# C3_0-_-3_0-led_-24_10_17.net
KiCad netlist of a schematic drawn in Altium Designer
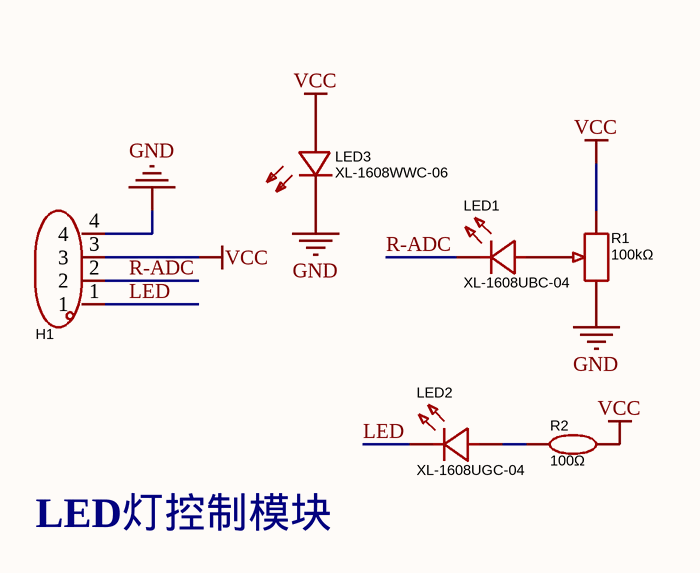
[diagram p0: C3.0-控制传感-3.0-led灯控制模块-24.10.17.SchDoc]

(export (version "E")
  (design (tool "Eeschema 10.0.6"))
  (components
    (comp (ref "H1")
      (value "PZ254V-11-04P")
      (footprint "HDR-TH_4P-P2.54-V-M")
      (fields (field (name "MANUFACTURER") "XFCN(兴飞)"))
      (libsource (lib "连接器") (part "PZ254V-11-04P"))
    )
    (comp (ref "LED1")
      (value "XL-1608UBC-04")
      (footprint "LED0603-RD_BLUE")
      (fields (field (name "MANUFACTURER") "XINGLIGHT(成兴光)"))
      (libsource (lib "外设") (part "XL-1608UBC-04"))
    )
    (comp (ref "LED2")
      (value "XL-1608UGC-04")
      (footprint "LED0603-RD_GREEN")
      (fields (field (name "MANUFACTURER") "XINGLIGHT(成兴光)"))
      (libsource (lib "外设") (part "XL-1608UGC-04"))
    )
    (comp (ref "LED3")
      (value "XL-1608WWC-06")
      (footprint "LED0603-RD_WHITE")
      (fields (field (name "MANUFACTURER") "XINGLIGHT(成兴光)"))
      (libsource (lib "外设") (part "XL-1608WWC-06"))
    )
    (comp (ref "R1")
      (value "100kΩ")
      (footprint "RES-ADJ-TH_3P-L9.5-W4.9-P2.50-L_3296W")
      (fields
        (field (name "MANUFACTURER") "BOCHEN(博晨)")
        (field (name "MANUFACTURER PART") "3296W-1-104")
        (field (name "TOLERANCE") "±10%")
      )
      (libsource (lib "电阻") (part "3296W-1-104"))
    )
    (comp (ref "R2")
      (value "100Ω")
      (footprint "R0805")
      (fields
        (field (name "MANUFACTURER") "UNI-ROYAL(厚声)")
        (field (name "MANUFACTURER PART") "0805W8F1000T5E")
        (field (name "TOLERANCE") "±1%")
      )
      (libsource (lib "电阻") (part "0805W8F1000T5E"))
    )
  )
  (nets
    (net (code "1") (name "/LED") (class "Default")
      (node (ref "H1") (pin "1") (pinfunction "1_1") (pintype "passive"))
      (node (ref "LED2") (pin "1") (pinfunction "K_1") (pintype "passive"))
    )
    (net (code "2") (name "/R-ADC") (class "Default")
      (node (ref "H1") (pin "2") (pinfunction "2_2") (pintype "passive"))
      (node (ref "LED1") (pin "1") (pinfunction "K_1") (pintype "passive"))
    )
    (net (code "3") (name "GND") (class "Default")
      (node (ref "H1") (pin "4") (pinfunction "4_4") (pintype "passive"))
      (node (ref "LED3") (pin "1") (pinfunction "C_1") (pintype "passive"))
      (node (ref "R1") (pin "1") (pinfunction "1_1") (pintype "passive"))
    )
    (net (code "4") (name "Net-(LED1-A)") (class "Default")
      (node (ref "LED1") (pin "2") (pinfunction "A_2") (pintype "passive"))
      (node (ref "R1") (pin "2") (pinfunction "2_2") (pintype "passive"))
    )
    (net (code "5") (name "Net-(LED2-A)") (class "Default")
      (node (ref "LED2") (pin "2") (pinfunction "A_2") (pintype "passive"))
      (node (ref "R2") (pin "1") (pinfunction "1_1") (pintype "passive"))
    )
    (net (code "6") (name "VCC") (class "Default")
      (node (ref "H1") (pin "3") (pinfunction "3_3") (pintype "passive"))
      (node (ref "LED3") (pin "2") (pinfunction "A_2") (pintype "passive"))
      (node (ref "R1") (pin "3") (pinfunction "3_3") (pintype "passive"))
      (node (ref "R2") (pin "2") (pinfunction "2_2") (pintype "passive"))
    )
  )
)
